# HA_Diagram.net
KiCad netlist of a schematic drawn in Altium Designer
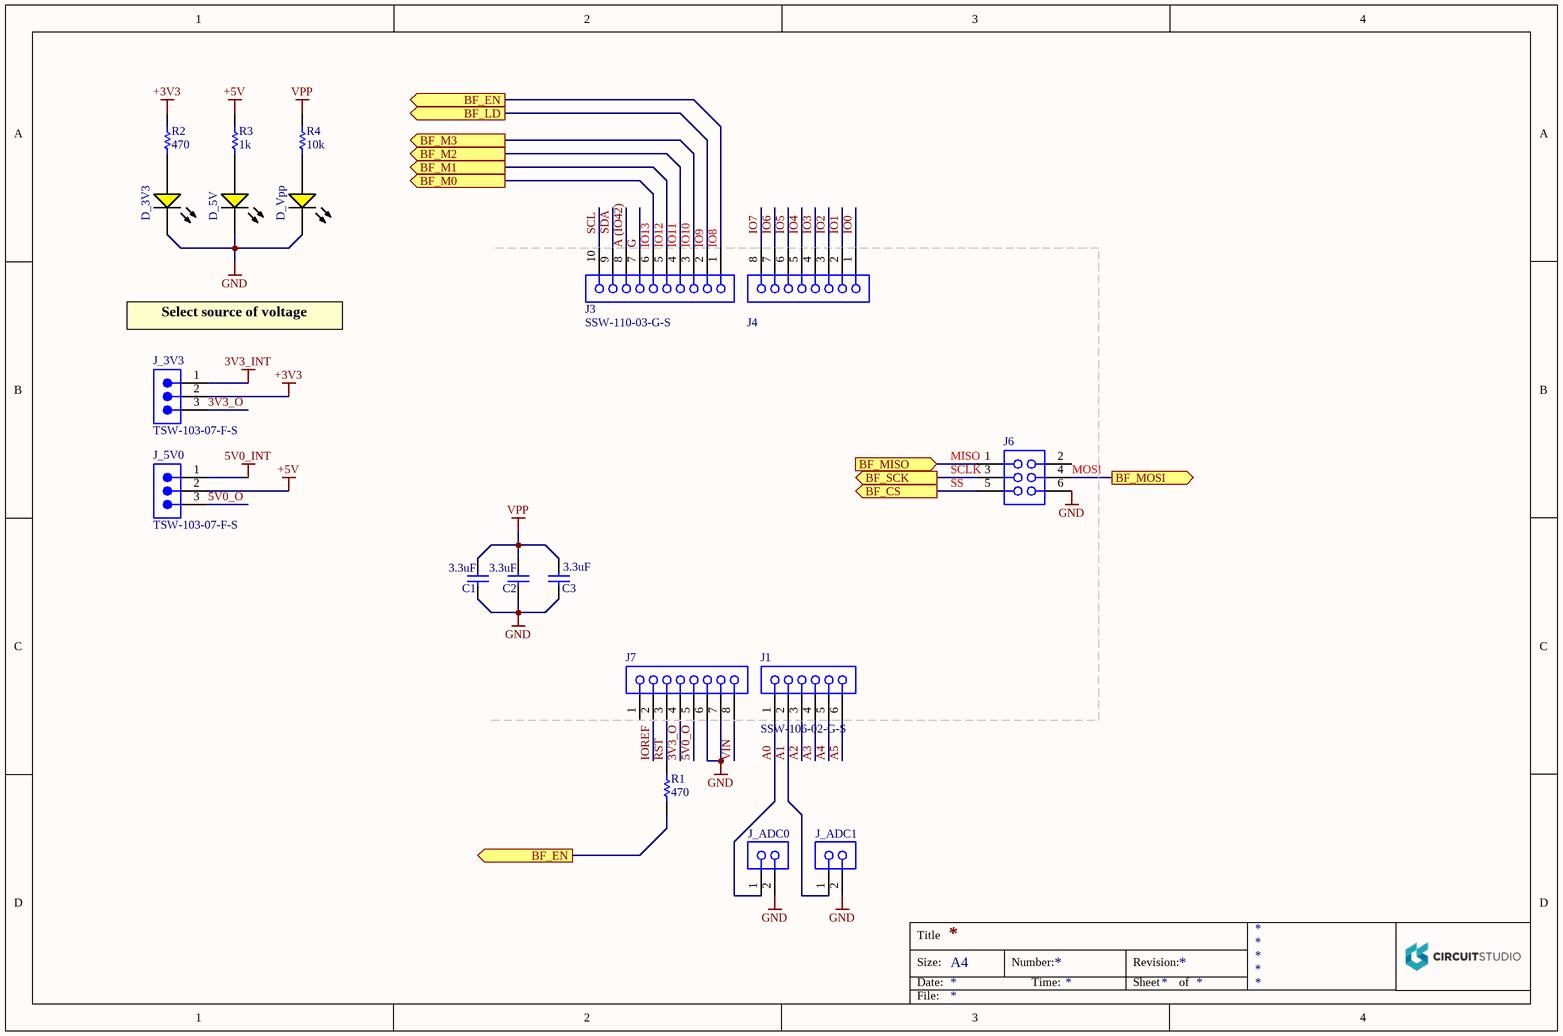
[diagram p0: HA_Diagram.SchDoc]

(export (version "E")
  (design (tool "Eeschema 10.0.6"))
  (components
    (comp (ref "C1")
      (value "3.3uF")
      (footprint "CAPC1206(3216)190_N")
      (description "CAP 3.3uF 100V ±20% 1206 (3216 Metric) Thickness 1.9mm SMD")
      (fields (field (name "TOLERANCE") "Â±20%") (field (name "Comment") "3.3uF 100V"))
      (libsource (lib "Altium Content Vault") (part "CMP-1037-04411-1"))
    )
    (comp (ref "C2")
      (value "3.3uF")
      (footprint "CAPC1206(3216)190_N")
      (description "CAP 3.3uF 100V ±20% 1206 (3216 Metric) Thickness 1.9mm SMD")
      (fields (field (name "TOLERANCE") "Â±20%") (field (name "Comment") "3.3uF 100V"))
      (libsource (lib "Altium Content Vault") (part "CMP-1037-04411-1"))
    )
    (comp (ref "C3")
      (value "3.3uF")
      (footprint "CAPC1206(3216)190_N")
      (description "CAP 3.3uF 100V ±20% 1206 (3216 Metric) Thickness 1.9mm SMD")
      (fields (field (name "TOLERANCE") "Â±20%") (field (name "Comment") "3.3uF 100V"))
      (libsource (lib "Altium Content Vault") (part "CMP-1037-04411-1"))
    )
    (comp (ref "D_3V3")
      (value "LED 0603")
      (footprint "LTST-C190KSKT_V")
      (fields (field (name "TOLERANCE") "1%"))
      (libsource (lib "Altium Content Vault") (part "CMP-1674-00009-1"))
    )
    (comp (ref "D_5V")
      (value "LED 0603")
      (footprint "LTST-C190KSKT_V")
      (fields (field (name "TOLERANCE") "1%"))
      (libsource (lib "Altium Content Vault") (part "CMP-1674-00009-1"))
    )
    (comp (ref "D_Vpp")
      (value "LED 0603")
      (footprint "LTST-C190KSKT_V")
      (fields (field (name "TOLERANCE") "1%"))
      (libsource (lib "Altium Content Vault") (part "CMP-1674-00009-1"))
    )
    (comp (ref "J1")
      (value "SSW-106-02-G-S")
      (footprint "SMTC-SSW-106-02-X-S")
      (description "SQ Post Socket, Through-hole, Vertical, -55 to 125 degC, 2.54mm Pitch, 6-Pin, Female, RoHS")
      (fields (field (name "MANUFACTURER") "Samtec"))
      (libsource (lib "Altium Content Vault") (part "CMP-1023-00359-1"))
    )
    (comp (ref "J3")
      (value "SSW-110-03-G-S")
      (footprint "SMTC-SSW-110-03-X-S")
      (description "SQ Post Socket, Through-hole, Vertical, -55 to 125 degC, 2.54 mm Pitch, 10-Pin, Female, RoHS")
      (fields (field (name "MANUFACTURER") "Samtec"))
      (libsource (lib "Altium Content Vault") (part "CMP-1023-00394-1"))
    )
    (comp (ref "J4")
      (value "SSQ-108-01-F-S")
      (footprint "SMTC-SSQ-108-01-X-S")
      (description "SQ Post Socket, Through-hole, Vertical, -55 to 125 degC, 2.54 mm Pitch, 8-Pin, Female, RoHS")
      (fields (field (name "MANUFACTURER") "Samtec"))
      (libsource (lib "Altium Content Vault") (part "CMP-1023-00294-1"))
    )
    (comp (ref "J6")
      (value "SSW-103-01-F-D")
      (footprint "SMTC-SSW-103-01-X-D")
      (description "SQ Post Socket, Through-hole, Vertical, -55 to 125 degC, 2.54 mm Pitch, 6-Pin, Female, RoHS")
      (fields (field (name "MANUFACTURER") "Samtec"))
      (libsource (lib "Altium Content Vault") (part "CMP-1023-00329-1"))
    )
    (comp (ref "J7")
      (value "SSQ-108-01-F-S")
      (footprint "SMTC-SSQ-108-01-X-S")
      (description "SQ Post Socket, Through-hole, Vertical, -55 to 125 degC, 2.54 mm Pitch, 8-Pin, Female, RoHS")
      (fields (field (name "MANUFACTURER") "Samtec"))
      (libsource (lib "Altium Content Vault") (part "CMP-1023-00294-1"))
    )
    (comp (ref "J_3V3")
      (value "TSW-103-07-F-S")
      (footprint "SMTC-TSW-103-07-X-S")
      (description "0.025\" SQ Post Header, Through-hole, Vertical, -55 to 125 degC, 2.54 mm Pitch, 3-Pin, Male, RoHS")
      (fields (field (name "MANUFACTURER") "Samtec"))
      (libsource (lib "Altium Content Vault") (part "CMP-1024-00331-1"))
    )
    (comp (ref "J_5V0")
      (value "TSW-103-07-F-S")
      (footprint "SMTC-TSW-103-07-X-S")
      (description "0.025\" SQ Post Header, Through-hole, Vertical, -55 to 125 degC, 2.54 mm Pitch, 3-Pin, Male, RoHS")
      (fields (field (name "MANUFACTURER") "Samtec"))
      (libsource (lib "Altium Content Vault") (part "CMP-1024-00331-1"))
    )
    (comp (ref "J_ADC0")
      (value "PHF-102-03-L-S")
      (footprint "SMTC-PHF-102-03-X-S")
      (description "Press Fit Socket, Through-hole, Vertical, -55 to 125 degC, 2.54 mm Pitch, 2-Pin, Female, RoHS")
      (fields (field (name "MANUFACTURER") "Samtec"))
      (libsource (lib "Altium Content Vault") (part "CMP-1023-00105-1"))
    )
    (comp (ref "J_ADC1")
      (value "PHF-102-03-L-S")
      (footprint "SMTC-PHF-102-03-X-S")
      (description "Press Fit Socket, Through-hole, Vertical, -55 to 125 degC, 2.54 mm Pitch, 2-Pin, Female, RoHS")
      (fields (field (name "MANUFACTURER") "Samtec"))
      (libsource (lib "Altium Content Vault") (part "CMP-1023-00105-1"))
    )
    (comp (ref "R1")
      (value "470")
      (footprint "RESC0603(1608)_N")
      (description "200 1% 0603 SMD")
      (fields (field (name "TOLERANCE") "1 %"))
      (libsource (lib "Altium Content Vault") (part "CMP-1012-00122-1"))
    )
    (comp (ref "R2")
      (value "470")
      (footprint "RESC0603(1608)_N")
      (description "200 1% 0603 SMD")
      (fields (field (name "TOLERANCE") "1 %"))
      (libsource (lib "Altium Content Vault") (part "CMP-1012-00122-1"))
    )
    (comp (ref "R3")
      (value "1k")
      (footprint "RESC0603(1608)_N")
      (description "200 1% 0603 SMD")
      (fields (field (name "TOLERANCE") "1 %"))
      (libsource (lib "Altium Content Vault") (part "CMP-1012-00122-1"))
    )
    (comp (ref "R4")
      (value "10k")
      (footprint "RESC0603(1608)_N")
      (description "200 1% 0603 SMD")
      (fields (field (name "TOLERANCE") "1 %"))
      (libsource (lib "Altium Content Vault") (part "CMP-1012-00122-1"))
    )
  )
  (nets
    (net (code "1") (name "+3V3") (class "Default")
      (node (ref "J_3V3") (pin "2") (pinfunction "2_2") (pintype "passive"))
      (node (ref "R2") (pin "1") (pinfunction "1_1") (pintype "passive"))
    )
    (net (code "2") (name "+5V") (class "Default")
      (node (ref "J_5V0") (pin "2") (pinfunction "2_2") (pintype "passive"))
      (node (ref "R3") (pin "1") (pinfunction "1_1") (pintype "passive"))
    )
    (net (code "3") (name "/3V3_O") (class "Default")
      (node (ref "J7") (pin "4") (pinfunction "4_4") (pintype "passive"))
      (node (ref "J_3V3") (pin "3") (pinfunction "3_3") (pintype "passive"))
    )
    (net (code "4") (name "/5V0_O") (class "Default")
      (node (ref "J7") (pin "5") (pinfunction "5_5") (pintype "passive"))
      (node (ref "J_5V0") (pin "3") (pinfunction "3_3") (pintype "passive"))
    )
    (net (code "5") (name "/A (IO42)") (class "Default")
      (node (ref "J3") (pin "8") (pinfunction "8_8") (pintype "passive"))
    )
    (net (code "6") (name "/A0") (class "Default")
      (node (ref "J1") (pin "1") (pinfunction "1_1") (pintype "passive"))
      (node (ref "J_ADC0") (pin "1") (pinfunction "1_1") (pintype "passive"))
    )
    (net (code "7") (name "/A1") (class "Default")
      (node (ref "J1") (pin "2") (pinfunction "2_2") (pintype "passive"))
      (node (ref "J_ADC1") (pin "1") (pinfunction "1_1") (pintype "passive"))
    )
    (net (code "8") (name "/A2") (class "Default")
      (node (ref "J1") (pin "3") (pinfunction "3_3") (pintype "passive"))
    )
    (net (code "9") (name "/A3") (class "Default")
      (node (ref "J1") (pin "4") (pinfunction "4_4") (pintype "passive"))
    )
    (net (code "10") (name "/A4") (class "Default")
      (node (ref "J1") (pin "5") (pinfunction "5_5") (pintype "passive"))
    )
    (net (code "11") (name "/A5") (class "Default")
      (node (ref "J1") (pin "6") (pinfunction "6_6") (pintype "passive"))
    )
    (net (code "12") (name "/BF_CS") (class "Default")
      (node (ref "J6") (pin "5") (pinfunction "5_5") (pintype "passive"))
    )
    (net (code "13") (name "/BF_EN") (class "Default")
      (node (ref "J3") (pin "1") (pinfunction "1_1") (pintype "passive"))
      (node (ref "R1") (pin "2") (pinfunction "2_2") (pintype "passive"))
    )
    (net (code "14") (name "/BF_LD") (class "Default")
      (node (ref "J3") (pin "2") (pinfunction "2_2") (pintype "passive"))
    )
    (net (code "15") (name "/BF_M0") (class "Default")
      (node (ref "J3") (pin "6") (pinfunction "6_6") (pintype "passive"))
    )
    (net (code "16") (name "/BF_M1") (class "Default")
      (node (ref "J3") (pin "5") (pinfunction "5_5") (pintype "passive"))
    )
    (net (code "17") (name "/BF_M2") (class "Default")
      (node (ref "J3") (pin "4") (pinfunction "4_4") (pintype "passive"))
    )
    (net (code "18") (name "/BF_M3") (class "Default")
      (node (ref "J3") (pin "3") (pinfunction "3_3") (pintype "passive"))
    )
    (net (code "19") (name "/BF_MISO") (class "Default")
      (node (ref "J6") (pin "1") (pinfunction "1_1") (pintype "passive"))
    )
    (net (code "20") (name "/BF_MOSI") (class "Default")
      (node (ref "J6") (pin "4") (pinfunction "4_4") (pintype "passive"))
    )
    (net (code "21") (name "/BF_SCK") (class "Default")
      (node (ref "J6") (pin "3") (pinfunction "3_3") (pintype "passive"))
    )
    (net (code "22") (name "/G") (class "Default")
      (node (ref "J3") (pin "7") (pinfunction "7_7") (pintype "passive"))
    )
    (net (code "23") (name "/IO0") (class "Default")
      (node (ref "J4") (pin "1") (pinfunction "1_1") (pintype "passive"))
    )
    (net (code "24") (name "/IO1") (class "Default")
      (node (ref "J4") (pin "2") (pinfunction "2_2") (pintype "passive"))
    )
    (net (code "25") (name "/IO2") (class "Default")
      (node (ref "J4") (pin "3") (pinfunction "3_3") (pintype "passive"))
    )
    (net (code "26") (name "/IO3") (class "Default")
      (node (ref "J4") (pin "4") (pinfunction "4_4") (pintype "passive"))
    )
    (net (code "27") (name "/IO4") (class "Default")
      (node (ref "J4") (pin "5") (pinfunction "5_5") (pintype "passive"))
    )
    (net (code "28") (name "/IO5") (class "Default")
      (node (ref "J4") (pin "6") (pinfunction "6_6") (pintype "passive"))
    )
    (net (code "29") (name "/IO6") (class "Default")
      (node (ref "J4") (pin "7") (pinfunction "7_7") (pintype "passive"))
    )
    (net (code "30") (name "/IO7") (class "Default")
      (node (ref "J4") (pin "8") (pinfunction "8_8") (pintype "passive"))
    )
    (net (code "31") (name "/IOREF") (class "Default")
      (node (ref "J7") (pin "2") (pinfunction "2_2") (pintype "passive"))
    )
    (net (code "32") (name "/RST") (class "Default")
      (node (ref "J7") (pin "3") (pinfunction "3_3") (pintype "passive"))
      (node (ref "R1") (pin "1") (pinfunction "1_1") (pintype "passive"))
    )
    (net (code "33") (name "/SCL") (class "Default")
      (node (ref "J3") (pin "10") (pinfunction "10_10") (pintype "passive"))
    )
    (net (code "34") (name "/SDA") (class "Default")
      (node (ref "J3") (pin "9") (pinfunction "9_9") (pintype "passive"))
    )
    (net (code "35") (name "/VIN") (class "Default")
      (node (ref "J7") (pin "8") (pinfunction "8_8") (pintype "passive"))
    )
    (net (code "36") (name "3V3_INT") (class "Default")
      (node (ref "J_3V3") (pin "1") (pinfunction "1_1") (pintype "passive"))
    )
    (net (code "37") (name "5V0_INT") (class "Default")
      (node (ref "J_5V0") (pin "1") (pinfunction "1_1") (pintype "passive"))
    )
    (net (code "38") (name "GND") (class "Default")
      (node (ref "C1") (pin "1") (pinfunction "1_1") (pintype "passive"))
      (node (ref "C2") (pin "1") (pinfunction "1_1") (pintype "passive"))
      (node (ref "C3") (pin "1") (pinfunction "1_1") (pintype "passive"))
      (node (ref "D_3V3") (pin "2") (pinfunction "K_2") (pintype "passive"))
      (node (ref "D_5V") (pin "2") (pinfunction "K_2") (pintype "passive"))
      (node (ref "D_Vpp") (pin "2") (pinfunction "K_2") (pintype "passive"))
      (node (ref "J6") (pin "6") (pinfunction "6_6") (pintype "passive"))
      (node (ref "J7") (pin "6") (pinfunction "6_6") (pintype "passive"))
      (node (ref "J7") (pin "7") (pinfunction "7_7") (pintype "passive"))
      (node (ref "J_ADC0") (pin "2") (pinfunction "2_2") (pintype "passive"))
      (node (ref "J_ADC1") (pin "2") (pinfunction "2_2") (pintype "passive"))
    )
    (net (code "39") (name "Net-(D_3V3-A)") (class "Default")
      (node (ref "D_3V3") (pin "1") (pinfunction "A_1") (pintype "passive"))
      (node (ref "R2") (pin "2") (pinfunction "2_2") (pintype "passive"))
    )
    (net (code "40") (name "Net-(D_5V-A)") (class "Default")
      (node (ref "D_5V") (pin "1") (pinfunction "A_1") (pintype "passive"))
      (node (ref "R3") (pin "2") (pinfunction "2_2") (pintype "passive"))
    )
    (net (code "41") (name "Net-(D_Vpp-A)") (class "Default")
      (node (ref "D_Vpp") (pin "1") (pinfunction "A_1") (pintype "passive"))
      (node (ref "R4") (pin "2") (pinfunction "2_2") (pintype "passive"))
    )
    (net (code "42") (name "VPP") (class "Default")
      (node (ref "C1") (pin "2") (pinfunction "2_2") (pintype "passive"))
      (node (ref "C2") (pin "2") (pinfunction "2_2") (pintype "passive"))
      (node (ref "C3") (pin "2") (pinfunction "2_2") (pintype "passive"))
      (node (ref "R4") (pin "1") (pinfunction "1_1") (pintype "passive"))
    )
    (net (code "43") (name "unconnected-(J6-Pad2)") (class "Default")
      (node (ref "J6") (pin "2") (pinfunction "2_2") (pintype "passive"))
    )
    (net (code "44") (name "unconnected-(J7-Pad1)") (class "Default")
      (node (ref "J7") (pin "1") (pinfunction "1_1") (pintype "passive"))
    )
  )
)
